# Lab_Controller_Board.net
KiCad netlist of a schematic drawn in EAGLE
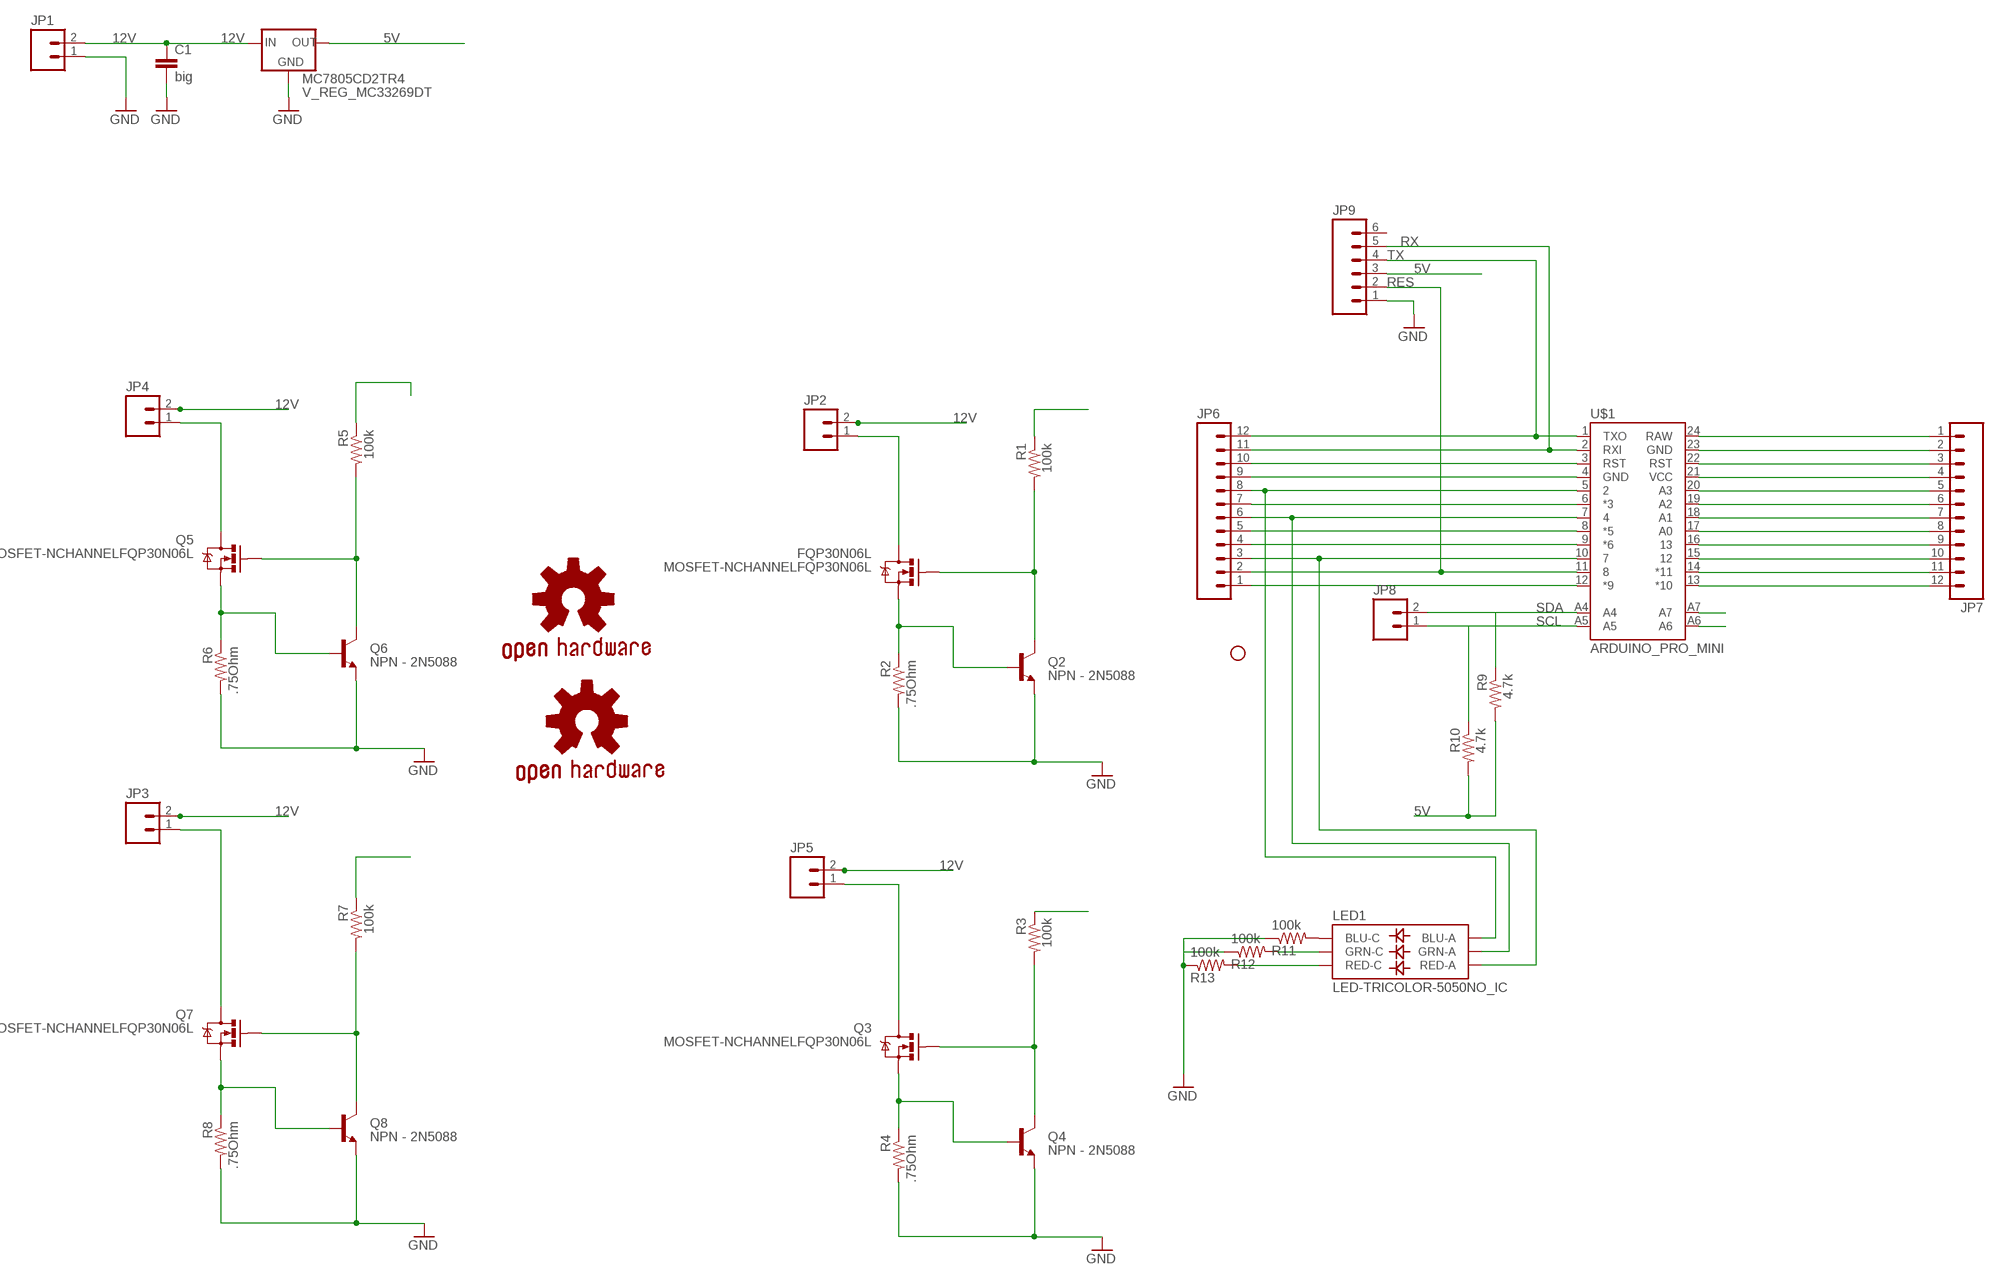
[diagram p0: schematic, sheet 1]

(export (version "E")
  (design (tool "Eeschema 10.0.6"))
  (components
    (comp (ref "C1")
      (value "big")
      (footprint "eagle-import:CAP-PTH-5MM")
      (libsource (lib "eagle-import") (part "CAPPTH1"))
    )
    (comp (ref "FQP30N06L")
      (value "MOSFET-NCHANNELFQP30N06L")
      (footprint "eagle-import:TO220V")
      (libsource (lib "eagle-import") (part "MOSFET-NCHANNELFQP30N06L"))
    )
    (comp (ref "GOLD_ORB_SM1")
      (value "OSHWLOGO_GOLD_ORB_MED")
      (footprint "eagle-import:OSHW1")
      (libsource (lib "eagle-import") (part "OSHWLOGO_GOLD_ORB_MED"))
    )
    (comp (ref "GOLD_ORB_SM2")
      (value "OSHWLOGO_GOLD_ORB_SM")
      (footprint "eagle-import:OSHW2")
      (libsource (lib "eagle-import") (part "OSHWLOGO_GOLD_ORB_SM"))
    )
    (comp (ref "JP1")
      (value "M025MM")
      (footprint "eagle-import:SCREWTERMINAL-5MM-2")
      (libsource (lib "eagle-import") (part "M025MM"))
    )
    (comp (ref "JP2")
      (value "M025MM")
      (footprint "eagle-import:SCREWTERMINAL-5MM-2")
      (libsource (lib "eagle-import") (part "M025MM"))
    )
    (comp (ref "JP3")
      (value "M025MM")
      (footprint "eagle-import:SCREWTERMINAL-5MM-2")
      (libsource (lib "eagle-import") (part "M025MM"))
    )
    (comp (ref "JP4")
      (value "M025MM")
      (footprint "eagle-import:SCREWTERMINAL-5MM-2")
      (libsource (lib "eagle-import") (part "M025MM"))
    )
    (comp (ref "JP5")
      (value "M025MM")
      (footprint "eagle-import:SCREWTERMINAL-5MM-2")
      (libsource (lib "eagle-import") (part "M025MM"))
    )
    (comp (ref "JP6")
      (value "M12PTH")
      (footprint "eagle-import:1X12")
      (libsource (lib "eagle-import") (part "M12PTH"))
    )
    (comp (ref "JP7")
      (value "M12PTH")
      (footprint "eagle-import:1X12")
      (libsource (lib "eagle-import") (part "M12PTH"))
    )
    (comp (ref "JP8")
      (value "M02LOCK")
      (footprint "eagle-import:1X02_LOCK")
      (libsource (lib "eagle-import") (part "M02LOCK"))
    )
    (comp (ref "JP9")
      (value "M06LOCK")
      (footprint "eagle-import:1X06_LOCK")
      (libsource (lib "eagle-import") (part "M06LOCK"))
    )
    (comp (ref "LED1")
      (value "LED-TRICOLOR-5050NO_IC")
      (footprint "eagle-import:LED-TRICOLOR-5050")
      (libsource (lib "eagle-import") (part "LED-TRICOLOR-5050NO_IC"))
    )
    (comp (ref "MC7805CD2TR4")
      (value "V_REG_MC33269DT")
      (footprint "eagle-import:DPAK")
      (libsource (lib "eagle-import") (part "V_REG_MC33269DT"))
    )
    (comp (ref "Q2")
      (value "NPN - 2N5088")
      (footprint "eagle-import:TO-92")
      (libsource (lib "eagle-import") (part "TRANSISTOR_NPNTO92"))
    )
    (comp (ref "Q3")
      (value "MOSFET-NCHANNELFQP30N06L")
      (footprint "eagle-import:TO220V")
      (libsource (lib "eagle-import") (part "MOSFET-NCHANNELFQP30N06L"))
    )
    (comp (ref "Q4")
      (value "NPN - 2N5088")
      (footprint "eagle-import:TO-92")
      (libsource (lib "eagle-import") (part "TRANSISTOR_NPNTO92"))
    )
    (comp (ref "Q5")
      (value "MOSFET-NCHANNELFQP30N06L")
      (footprint "eagle-import:TO220V")
      (libsource (lib "eagle-import") (part "MOSFET-NCHANNELFQP30N06L"))
    )
    (comp (ref "Q6")
      (value "NPN - 2N5088")
      (footprint "eagle-import:TO-92")
      (libsource (lib "eagle-import") (part "TRANSISTOR_NPNTO92"))
    )
    (comp (ref "Q7")
      (value "MOSFET-NCHANNELFQP30N06L")
      (footprint "eagle-import:TO220V")
      (libsource (lib "eagle-import") (part "MOSFET-NCHANNELFQP30N06L"))
    )
    (comp (ref "Q8")
      (value "NPN - 2N5088")
      (footprint "eagle-import:TO-92")
      (libsource (lib "eagle-import") (part "TRANSISTOR_NPNTO92"))
    )
    (comp (ref "R1")
      (value "100k")
      (footprint "eagle-import:R0805W")
      (libsource (lib "eagle-import") (part "R-US_R0805W"))
    )
    (comp (ref "R2")
      (value ".75Ohm")
      (footprint "eagle-import:0411V")
      (libsource (lib "eagle-import") (part "R-US_0411/3V"))
    )
    (comp (ref "R3")
      (value "100k")
      (footprint "eagle-import:R0805W")
      (libsource (lib "eagle-import") (part "R-US_R0805W"))
    )
    (comp (ref "R4")
      (value ".75Ohm")
      (footprint "eagle-import:0411V")
      (libsource (lib "eagle-import") (part "R-US_0411/3V"))
    )
    (comp (ref "R5")
      (value "100k")
      (footprint "eagle-import:R0805W")
      (libsource (lib "eagle-import") (part "R-US_R0805W"))
    )
    (comp (ref "R6")
      (value ".75Ohm")
      (footprint "eagle-import:0411V")
      (libsource (lib "eagle-import") (part "R-US_0411/3V"))
    )
    (comp (ref "R7")
      (value "100k")
      (footprint "eagle-import:R0805W")
      (libsource (lib "eagle-import") (part "R-US_R0805W"))
    )
    (comp (ref "R8")
      (value ".75Ohm")
      (footprint "eagle-import:0411V")
      (libsource (lib "eagle-import") (part "R-US_0411/3V"))
    )
    (comp (ref "R9")
      (value "4.7k")
      (footprint "eagle-import:M0805")
      (libsource (lib "eagle-import") (part "R-US_M0805"))
    )
    (comp (ref "R10")
      (value "4.7k")
      (footprint "eagle-import:M0805")
      (libsource (lib "eagle-import") (part "R-US_M0805"))
    )
    (comp (ref "R11")
      (value "100k")
      (footprint "eagle-import:R0805W")
      (libsource (lib "eagle-import") (part "R-US_R0805W"))
    )
    (comp (ref "R12")
      (value "100k")
      (footprint "eagle-import:R0805W")
      (libsource (lib "eagle-import") (part "R-US_R0805W"))
    )
    (comp (ref "R13")
      (value "100k")
      (footprint "eagle-import:R0805W")
      (libsource (lib "eagle-import") (part "R-US_R0805W"))
    )
    (comp (ref "STANDOFF1")
      (value "STAND-OFF")
      (footprint "eagle-import:STAND-OFF")
      (libsource (lib "eagle-import") (part "STAND-OFF"))
    )
    (comp (ref "U$1")
      (value "ARDUINO_PRO_MINI")
      (footprint "eagle-import:ARDUINO_PRO_MINI")
      (libsource (lib "eagle-import") (part "ARDUINO_PRO_MINI"))
    )
  )
  (nets
    (net (code "1") (name "/5V") (class "Default")
      (node (ref "JP9") (pin "3") (pinfunction "3_3") (pintype "passive"))
      (node (ref "MC7805CD2TR4") (pin "4") (pinfunction "OUT_4") (pintype "passive"))
      (node (ref "R10") (pin "2") (pinfunction "2_2") (pintype "passive"))
      (node (ref "R9") (pin "2") (pinfunction "2_2") (pintype "passive"))
    )
    (net (code "2") (name "/12V") (class "Default")
      (node (ref "C1") (pin "1") (pinfunction "1_1") (pintype "passive"))
      (node (ref "JP1") (pin "2") (pinfunction "2_2") (pintype "passive"))
      (node (ref "JP2") (pin "2") (pinfunction "2_2") (pintype "passive"))
      (node (ref "JP3") (pin "2") (pinfunction "2_2") (pintype "passive"))
      (node (ref "JP4") (pin "2") (pinfunction "2_2") (pintype "passive"))
      (node (ref "JP5") (pin "2") (pinfunction "2_2") (pintype "passive"))
      (node (ref "MC7805CD2TR4") (pin "3") (pinfunction "IN_3") (pintype "input"))
    )
    (net (code "3") (name "/APM_PIN_3") (class "Default")
      (node (ref "JP6") (pin "7") (pinfunction "7_7") (pintype "passive"))
      (node (ref "R3") (pin "1") (pinfunction "1_1") (pintype "passive"))
      (node (ref "U$1") (pin "6") (pinfunction "*3_6") (pintype "bidirectional"))
    )
    (net (code "4") (name "/APM_PIN_5") (class "Default")
      (node (ref "JP6") (pin "5") (pinfunction "5_5") (pintype "passive"))
      (node (ref "R1") (pin "1") (pinfunction "1_1") (pintype "passive"))
      (node (ref "U$1") (pin "8") (pinfunction "*5_8") (pintype "bidirectional"))
    )
    (net (code "5") (name "/APM_PIN_6") (class "Default")
      (node (ref "JP6") (pin "4") (pinfunction "4_4") (pintype "passive"))
      (node (ref "R7") (pin "1") (pinfunction "1_1") (pintype "passive"))
      (node (ref "U$1") (pin "9") (pinfunction "*6_9") (pintype "bidirectional"))
    )
    (net (code "6") (name "/APM_PIN_9") (class "Default")
      (node (ref "JP6") (pin "1") (pinfunction "1_1") (pintype "passive"))
      (node (ref "R5") (pin "1") (pinfunction "1_1") (pintype "passive"))
      (node (ref "U$1") (pin "12") (pinfunction "*9_12") (pintype "bidirectional"))
    )
    (net (code "7") (name "/RES") (class "Default")
      (node (ref "JP6") (pin "2") (pinfunction "2_2") (pintype "passive"))
      (node (ref "JP9") (pin "2") (pinfunction "2_2") (pintype "passive"))
      (node (ref "U$1") (pin "11") (pinfunction "8_11") (pintype "bidirectional"))
    )
    (net (code "8") (name "/RX") (class "Default")
      (node (ref "JP6") (pin "11") (pinfunction "11_11") (pintype "passive"))
      (node (ref "JP9") (pin "5") (pinfunction "5_5") (pintype "passive"))
      (node (ref "U$1") (pin "2") (pinfunction "RXI_2") (pintype "bidirectional"))
    )
    (net (code "9") (name "/SCL") (class "Default")
      (node (ref "JP8") (pin "1") (pinfunction "1_1") (pintype "passive"))
      (node (ref "R10") (pin "1") (pinfunction "1_1") (pintype "passive"))
      (node (ref "U$1") (pin "A5") (pinfunction "A5_A5") (pintype "bidirectional"))
    )
    (net (code "10") (name "/SDA") (class "Default")
      (node (ref "JP8") (pin "2") (pinfunction "2_2") (pintype "passive"))
      (node (ref "R9") (pin "1") (pinfunction "1_1") (pintype "passive"))
      (node (ref "U$1") (pin "A4") (pinfunction "A4_A4") (pintype "bidirectional"))
    )
    (net (code "11") (name "/TX") (class "Default")
      (node (ref "JP6") (pin "12") (pinfunction "12_12") (pintype "passive"))
      (node (ref "JP9") (pin "4") (pinfunction "4_4") (pintype "passive"))
      (node (ref "U$1") (pin "1") (pinfunction "TXO_1") (pintype "bidirectional"))
    )
    (net (code "12") (name "GND") (class "Default")
      (node (ref "C1") (pin "2") (pinfunction "2_2") (pintype "passive"))
      (node (ref "JP1") (pin "1") (pinfunction "1_1") (pintype "passive"))
      (node (ref "JP9") (pin "1") (pinfunction "1_1") (pintype "passive"))
      (node (ref "MC7805CD2TR4") (pin "1") (pinfunction "GND_1") (pintype "input"))
      (node (ref "Q2") (pin "1") (pinfunction "E_1") (pintype "passive"))
      (node (ref "Q4") (pin "1") (pinfunction "E_1") (pintype "passive"))
      (node (ref "Q6") (pin "1") (pinfunction "E_1") (pintype "passive"))
      (node (ref "Q8") (pin "1") (pinfunction "E_1") (pintype "passive"))
      (node (ref "R11") (pin "1") (pinfunction "1_1") (pintype "passive"))
      (node (ref "R12") (pin "1") (pinfunction "1_1") (pintype "passive"))
      (node (ref "R13") (pin "1") (pinfunction "1_1") (pintype "passive"))
      (node (ref "R2") (pin "2") (pinfunction "2_2") (pintype "passive"))
      (node (ref "R4") (pin "2") (pinfunction "2_2") (pintype "passive"))
      (node (ref "R6") (pin "2") (pinfunction "2_2") (pintype "passive"))
      (node (ref "R8") (pin "2") (pinfunction "2_2") (pintype "passive"))
    )
    (net (code "13") (name "Net-(FQP30N06L-D)") (class "Default")
      (node (ref "FQP30N06L") (pin "2") (pinfunction "D_2") (pintype "passive"))
      (node (ref "JP2") (pin "1") (pinfunction "1_1") (pintype "passive"))
    )
    (net (code "14") (name "Net-(FQP30N06L-G)") (class "Default")
      (node (ref "FQP30N06L") (pin "1") (pinfunction "G_1") (pintype "passive"))
      (node (ref "Q2") (pin "3") (pinfunction "C_3") (pintype "passive"))
      (node (ref "R1") (pin "2") (pinfunction "2_2") (pintype "passive"))
    )
    (net (code "15") (name "Net-(FQP30N06L-S)") (class "Default")
      (node (ref "FQP30N06L") (pin "3") (pinfunction "S_3") (pintype "passive"))
      (node (ref "Q2") (pin "2") (pinfunction "B_2") (pintype "passive"))
      (node (ref "R2") (pin "1") (pinfunction "1_1") (pintype "passive"))
    )
    (net (code "16") (name "Net-(JP6-Pad9)") (class "Default")
      (node (ref "JP6") (pin "9") (pinfunction "9_9") (pintype "passive"))
      (node (ref "U$1") (pin "4") (pinfunction "GND_4") (pintype "bidirectional"))
    )
    (net (code "17") (name "Net-(JP6-Pad10)") (class "Default")
      (node (ref "JP6") (pin "10") (pinfunction "10_10") (pintype "passive"))
      (node (ref "U$1") (pin "3") (pinfunction "RST_3") (pintype "bidirectional"))
    )
    (net (code "18") (name "Net-(JP7-Pad2)") (class "Default")
      (node (ref "JP7") (pin "2") (pinfunction "2_2") (pintype "passive"))
      (node (ref "U$1") (pin "23") (pinfunction "GND_23") (pintype "bidirectional"))
    )
    (net (code "19") (name "Net-(JP7-Pad3)") (class "Default")
      (node (ref "JP7") (pin "3") (pinfunction "3_3") (pintype "passive"))
      (node (ref "U$1") (pin "22") (pinfunction "RST_22") (pintype "bidirectional"))
    )
    (net (code "20") (name "Net-(LED1-BLU-A)") (class "Default")
      (node (ref "JP6") (pin "8") (pinfunction "8_8") (pintype "passive"))
      (node (ref "LED1") (pin "3") (pinfunction "BLU-A_3") (pintype "bidirectional"))
      (node (ref "U$1") (pin "5") (pinfunction "2_5") (pintype "bidirectional"))
    )
    (net (code "21") (name "Net-(LED1-BLU-C)") (class "Default")
      (node (ref "LED1") (pin "4") (pinfunction "BLU-C_4") (pintype "bidirectional"))
      (node (ref "R11") (pin "2") (pinfunction "2_2") (pintype "passive"))
    )
    (net (code "22") (name "Net-(LED1-GRN-A)") (class "Default")
      (node (ref "JP6") (pin "6") (pinfunction "6_6") (pintype "passive"))
      (node (ref "LED1") (pin "1") (pinfunction "GRN-A_1") (pintype "bidirectional"))
      (node (ref "U$1") (pin "7") (pinfunction "4_7") (pintype "bidirectional"))
    )
    (net (code "23") (name "Net-(LED1-GRN-C)") (class "Default")
      (node (ref "LED1") (pin "6") (pinfunction "GRN-C_6") (pintype "bidirectional"))
      (node (ref "R12") (pin "2") (pinfunction "2_2") (pintype "passive"))
    )
    (net (code "24") (name "Net-(LED1-RED-A)") (class "Default")
      (node (ref "JP6") (pin "3") (pinfunction "3_3") (pintype "passive"))
      (node (ref "LED1") (pin "2") (pinfunction "RED-A_2") (pintype "bidirectional"))
      (node (ref "U$1") (pin "10") (pinfunction "7_10") (pintype "bidirectional"))
    )
    (net (code "25") (name "Net-(LED1-RED-C)") (class "Default")
      (node (ref "LED1") (pin "5") (pinfunction "RED-C_5") (pintype "bidirectional"))
      (node (ref "R13") (pin "2") (pinfunction "2_2") (pintype "passive"))
    )
    (net (code "26") (name "Net-(Q3-D)") (class "Default")
      (node (ref "JP5") (pin "1") (pinfunction "1_1") (pintype "passive"))
      (node (ref "Q3") (pin "2") (pinfunction "D_2") (pintype "passive"))
    )
    (net (code "27") (name "Net-(Q3-G)") (class "Default")
      (node (ref "Q3") (pin "1") (pinfunction "G_1") (pintype "passive"))
      (node (ref "Q4") (pin "3") (pinfunction "C_3") (pintype "passive"))
      (node (ref "R3") (pin "2") (pinfunction "2_2") (pintype "passive"))
    )
    (net (code "28") (name "Net-(Q3-S)") (class "Default")
      (node (ref "Q3") (pin "3") (pinfunction "S_3") (pintype "passive"))
      (node (ref "Q4") (pin "2") (pinfunction "B_2") (pintype "passive"))
      (node (ref "R4") (pin "1") (pinfunction "1_1") (pintype "passive"))
    )
    (net (code "29") (name "Net-(Q5-D)") (class "Default")
      (node (ref "JP4") (pin "1") (pinfunction "1_1") (pintype "passive"))
      (node (ref "Q5") (pin "2") (pinfunction "D_2") (pintype "passive"))
    )
    (net (code "30") (name "Net-(Q5-G)") (class "Default")
      (node (ref "Q5") (pin "1") (pinfunction "G_1") (pintype "passive"))
      (node (ref "Q6") (pin "3") (pinfunction "C_3") (pintype "passive"))
      (node (ref "R5") (pin "2") (pinfunction "2_2") (pintype "passive"))
    )
    (net (code "31") (name "Net-(Q5-S)") (class "Default")
      (node (ref "Q5") (pin "3") (pinfunction "S_3") (pintype "passive"))
      (node (ref "Q6") (pin "2") (pinfunction "B_2") (pintype "passive"))
      (node (ref "R6") (pin "1") (pinfunction "1_1") (pintype "passive"))
    )
    (net (code "32") (name "Net-(Q7-D)") (class "Default")
      (node (ref "JP3") (pin "1") (pinfunction "1_1") (pintype "passive"))
      (node (ref "Q7") (pin "2") (pinfunction "D_2") (pintype "passive"))
    )
    (net (code "33") (name "Net-(Q7-G)") (class "Default")
      (node (ref "Q7") (pin "1") (pinfunction "G_1") (pintype "passive"))
      (node (ref "Q8") (pin "3") (pinfunction "C_3") (pintype "passive"))
      (node (ref "R7") (pin "2") (pinfunction "2_2") (pintype "passive"))
    )
    (net (code "34") (name "Net-(Q7-S)") (class "Default")
      (node (ref "Q7") (pin "3") (pinfunction "S_3") (pintype "passive"))
      (node (ref "Q8") (pin "2") (pinfunction "B_2") (pintype "passive"))
      (node (ref "R8") (pin "1") (pinfunction "1_1") (pintype "passive"))
    )
    (net (code "35") (name "Net-(U$1-*10)") (class "Default")
      (node (ref "JP7") (pin "12") (pinfunction "12_12") (pintype "passive"))
      (node (ref "U$1") (pin "13") (pinfunction "*10_13") (pintype "bidirectional"))
    )
    (net (code "36") (name "Net-(U$1-*11)") (class "Default")
      (node (ref "JP7") (pin "11") (pinfunction "11_11") (pintype "passive"))
      (node (ref "U$1") (pin "14") (pinfunction "*11_14") (pintype "bidirectional"))
    )
    (net (code "37") (name "Net-(U$1-12)") (class "Default")
      (node (ref "JP7") (pin "10") (pinfunction "10_10") (pintype "passive"))
      (node (ref "U$1") (pin "15") (pinfunction "12_15") (pintype "bidirectional"))
    )
    (net (code "38") (name "Net-(U$1-13)") (class "Default")
      (node (ref "JP7") (pin "9") (pinfunction "9_9") (pintype "passive"))
      (node (ref "U$1") (pin "16") (pinfunction "13_16") (pintype "bidirectional"))
    )
    (net (code "39") (name "Net-(U$1-A0)") (class "Default")
      (node (ref "JP7") (pin "8") (pinfunction "8_8") (pintype "passive"))
      (node (ref "U$1") (pin "17") (pinfunction "A0_17") (pintype "bidirectional"))
    )
    (net (code "40") (name "Net-(U$1-A1)") (class "Default")
      (node (ref "JP7") (pin "7") (pinfunction "7_7") (pintype "passive"))
      (node (ref "U$1") (pin "18") (pinfunction "A1_18") (pintype "bidirectional"))
    )
    (net (code "41") (name "Net-(U$1-A2)") (class "Default")
      (node (ref "JP7") (pin "6") (pinfunction "6_6") (pintype "passive"))
      (node (ref "U$1") (pin "19") (pinfunction "A2_19") (pintype "bidirectional"))
    )
    (net (code "42") (name "Net-(U$1-A3)") (class "Default")
      (node (ref "JP7") (pin "5") (pinfunction "5_5") (pintype "passive"))
      (node (ref "U$1") (pin "20") (pinfunction "A3_20") (pintype "bidirectional"))
    )
    (net (code "43") (name "Net-(U$1-RAW)") (class "Default")
      (node (ref "JP7") (pin "1") (pinfunction "1_1") (pintype "passive"))
      (node (ref "U$1") (pin "24") (pinfunction "RAW_24") (pintype "bidirectional"))
    )
    (net (code "44") (name "Net-(U$1-VCC)") (class "Default")
      (node (ref "JP7") (pin "4") (pinfunction "4_4") (pintype "passive"))
      (node (ref "U$1") (pin "21") (pinfunction "VCC_21") (pintype "bidirectional"))
    )
    (net (code "45") (name "unconnected-(JP9-Pad6)") (class "Default")
      (node (ref "JP9") (pin "6") (pinfunction "6_6") (pintype "passive"))
    )
    (net (code "46") (name "unconnected-(U$1-PadA6)") (class "Default")
      (node (ref "U$1") (pin "A6") (pinfunction "A6_A6") (pintype "bidirectional"))
    )
    (net (code "47") (name "unconnected-(U$1-PadA7)") (class "Default")
      (node (ref "U$1") (pin "A7") (pinfunction "A7_A7") (pintype "bidirectional"))
    )
  )
)
